# proxy.net
KiCad netlist of a schematic drawn in EAGLE
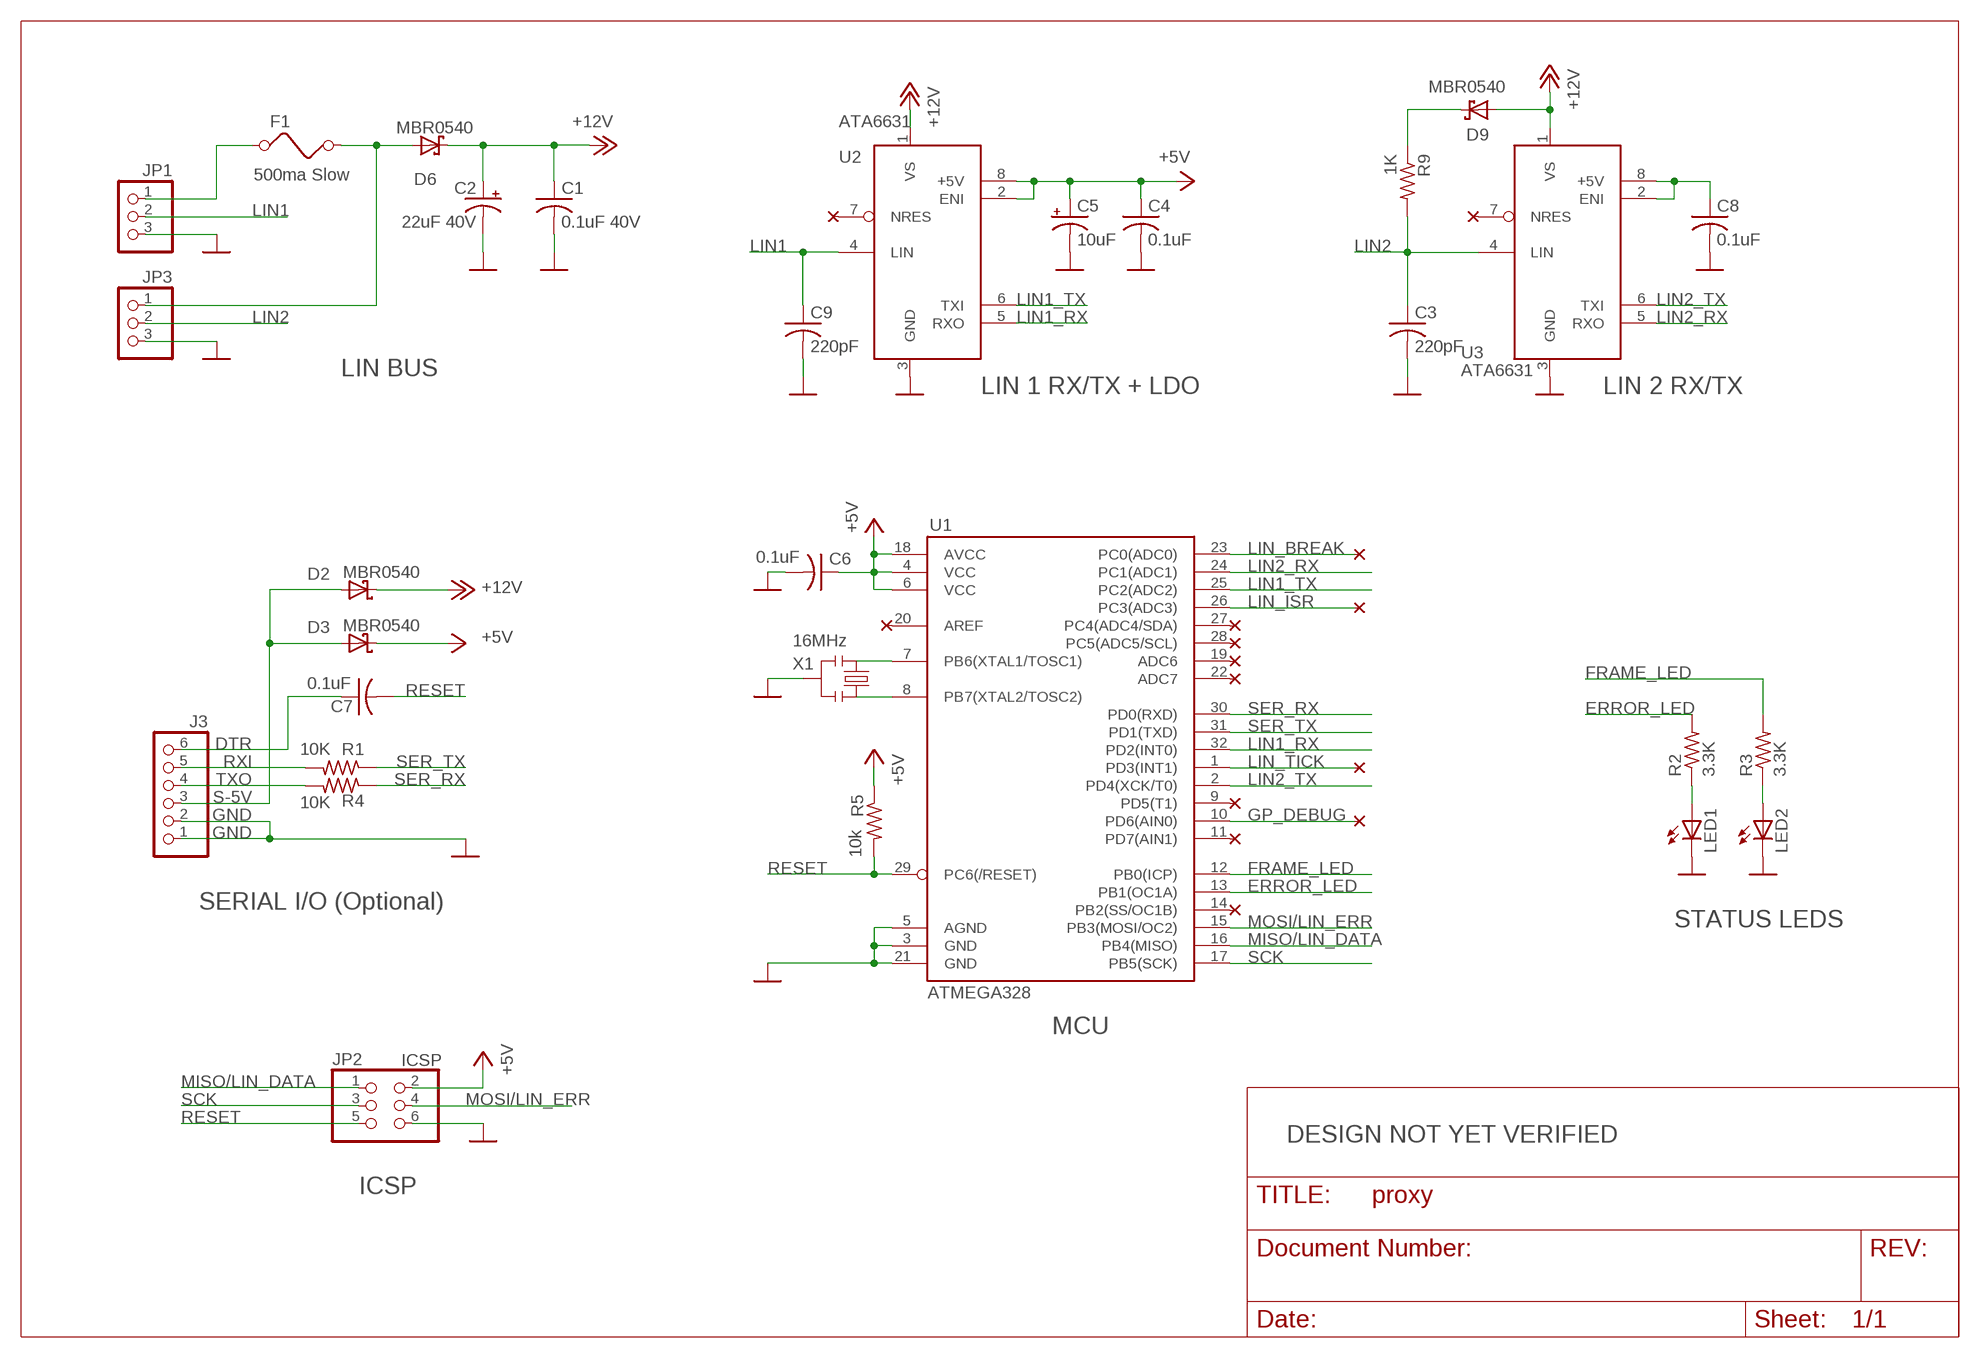
[diagram p0: schematic, sheet 1]

(export (version "E")
  (design (tool "Eeschema 10.0.6"))
  (components
    (comp (ref "C1")
      (value "0.1uF 40V")
      (footprint "eagle-import:C0805")
      (libsource (lib "eagle-import") (part "C-USC0805"))
    )
    (comp (ref "C2")
      (value "22uF 40V")
      (footprint "eagle-import:UD-6,3X5,8_NICHICON")
      (libsource (lib "eagle-import") (part "CPOL-USUD-6,3X5,8"))
    )
    (comp (ref "C3")
      (value "220pF")
      (footprint "eagle-import:C0805")
      (libsource (lib "eagle-import") (part "C-USC0805"))
    )
    (comp (ref "C4")
      (value "0.1uF")
      (footprint "eagle-import:C0805")
      (libsource (lib "eagle-import") (part "C-USC0805"))
    )
    (comp (ref "C5")
      (value "10uF")
      (footprint "eagle-import:A_3216-18R")
      (libsource (lib "eagle-import") (part "CPOL-USA/3216-18R"))
    )
    (comp (ref "C6")
      (value "0.1uF")
      (footprint "eagle-import:C0805")
      (libsource (lib "eagle-import") (part "C-USC0805"))
    )
    (comp (ref "C7")
      (value "0.1uF")
      (footprint "eagle-import:C0805")
      (libsource (lib "eagle-import") (part "C-USC0805"))
    )
    (comp (ref "C8")
      (value "0.1uF")
      (footprint "eagle-import:C0805")
      (libsource (lib "eagle-import") (part "C-USC0805"))
    )
    (comp (ref "C9")
      (value "220pF")
      (footprint "eagle-import:C0805")
      (libsource (lib "eagle-import") (part "C-USC0805"))
    )
    (comp (ref "D2")
      (value "MBR0540")
      (footprint "eagle-import:SOD123FL")
      (libsource (lib "eagle-import") (part "SMF5.0AT1"))
    )
    (comp (ref "D3")
      (value "MBR0540")
      (footprint "eagle-import:SOD123FL")
      (libsource (lib "eagle-import") (part "SMF5.0AT1"))
    )
    (comp (ref "D6")
      (value "MBR0540")
      (footprint "eagle-import:SOD123FL")
      (libsource (lib "eagle-import") (part "SMF5.0AT1"))
    )
    (comp (ref "D9")
      (value "MBR0540")
      (footprint "eagle-import:SOD123FL")
      (libsource (lib "eagle-import") (part "SMF5.0AT1"))
    )
    (comp (ref "F1")
      (value "500ma Slow")
      (footprint "eagle-import:1206")
      (libsource (lib "eagle-import") (part "FUSE"))
    )
    (comp (ref "J3")
      (value "PINHD-1X6")
      (footprint "eagle-import:1X06")
      (libsource (lib "eagle-import") (part "PINHD-1X6"))
    )
    (comp (ref "JP1")
      (value "PINHD-1X3")
      (footprint "eagle-import:1X03")
      (libsource (lib "eagle-import") (part "PINHD-1X3"))
    )
    (comp (ref "JP2")
      (value "ICSP")
      (footprint "eagle-import:2X03")
      (libsource (lib "eagle-import") (part "PINHD-2X3"))
    )
    (comp (ref "JP3")
      (value "PINHD-1X3")
      (footprint "eagle-import:1X03")
      (libsource (lib "eagle-import") (part "PINHD-1X3"))
    )
    (comp (ref "LED1")
      (value "LED")
      (footprint "eagle-import:1206-LED")
      (libsource (lib "eagle-import") (part "LED"))
    )
    (comp (ref "LED2")
      (value "LED")
      (footprint "eagle-import:1206-LED")
      (libsource (lib "eagle-import") (part "LED"))
    )
    (comp (ref "R1")
      (value "10K")
      (footprint "eagle-import:R0805")
      (libsource (lib "eagle-import") (part "R-US_R0805"))
    )
    (comp (ref "R2")
      (value "3.3K")
      (footprint "eagle-import:R0805")
      (libsource (lib "eagle-import") (part "R-US_R0805"))
    )
    (comp (ref "R3")
      (value "3.3K")
      (footprint "eagle-import:R0805")
      (libsource (lib "eagle-import") (part "R-US_R0805"))
    )
    (comp (ref "R4")
      (value "10K")
      (footprint "eagle-import:R0805")
      (libsource (lib "eagle-import") (part "R-US_R0805"))
    )
    (comp (ref "R5")
      (value "10k")
      (footprint "eagle-import:R0805")
      (libsource (lib "eagle-import") (part "R-US_R0805"))
    )
    (comp (ref "R9")
      (value "1K")
      (footprint "eagle-import:R0805")
      (libsource (lib "eagle-import") (part "R-US_R0805"))
    )
    (comp (ref "U1")
      (value "ATMEGA328")
      (footprint "eagle-import:TQFP32-08")
      (libsource (lib "eagle-import") (part "ATMEGA328"))
    )
    (comp (ref "U2")
      (value "ATA6631")
      (footprint "eagle-import:SO-08")
      (libsource (lib "eagle-import") (part "ATA6631"))
    )
    (comp (ref "U3")
      (value "ATA6631")
      (footprint "eagle-import:SO-08")
      (libsource (lib "eagle-import") (part "ATA6631"))
    )
    (comp (ref "X1")
      (value "16MHz")
      (footprint "eagle-import:RESONATOR-SMD")
      (libsource (lib "eagle-import") (part "RESONATORSMD"))
    )
  )
  (nets
    (net (code "1") (name "+5V") (class "Default")
      (node (ref "C4") (pin "1") (pinfunction "1_1") (pintype "passive"))
      (node (ref "C5") (pin "+") (pinfunction "+_+") (pintype "passive"))
      (node (ref "C6") (pin "1") (pinfunction "1_1") (pintype "passive"))
      (node (ref "D3") (pin "C") (pinfunction "C_C") (pintype "passive"))
      (node (ref "JP2") (pin "2") (pinfunction "2_2") (pintype "passive"))
      (node (ref "R5") (pin "1") (pinfunction "1_1") (pintype "passive"))
      (node (ref "U1") (pin "18") (pinfunction "AVCC_18") (pintype "power_in"))
      (node (ref "U1") (pin "4") (pinfunction "VCC_4") (pintype "power_in"))
      (node (ref "U1") (pin "6") (pinfunction "VCC_6") (pintype "power_in"))
      (node (ref "U2") (pin "2") (pinfunction "ENI_2") (pintype "input"))
      (node (ref "U2") (pin "8") (pinfunction "+5V_8") (pintype "power_in"))
    )
    (net (code "2") (name "+12V") (class "Default")
      (node (ref "C1") (pin "1") (pinfunction "1_1") (pintype "passive"))
      (node (ref "C2") (pin "+") (pinfunction "+_+") (pintype "passive"))
      (node (ref "D2") (pin "C") (pinfunction "C_C") (pintype "passive"))
      (node (ref "D6") (pin "C") (pinfunction "C_C") (pintype "passive"))
      (node (ref "D9") (pin "A") (pinfunction "A_A") (pintype "passive"))
      (node (ref "U2") (pin "1") (pinfunction "VS_1") (pintype "power_in"))
      (node (ref "U3") (pin "1") (pinfunction "VS_1") (pintype "power_in"))
    )
    (net (code "3") (name "/AREF") (class "Default")
      (node (ref "U1") (pin "20") (pinfunction "AREF_20") (pintype "power_in"))
    )
    (net (code "4") (name "/DTR") (class "Default")
      (node (ref "C7") (pin "1") (pinfunction "1_1") (pintype "passive"))
      (node (ref "J3") (pin "6") (pinfunction "6_6") (pintype "passive"))
    )
    (net (code "5") (name "/ERROR_LED") (class "Default")
      (node (ref "R2") (pin "2") (pinfunction "2_2") (pintype "passive"))
      (node (ref "U1") (pin "13") (pinfunction "PB1(OC1A)_13") (pintype "bidirectional"))
    )
    (net (code "6") (name "/FRAME_LED") (class "Default")
      (node (ref "R3") (pin "2") (pinfunction "2_2") (pintype "passive"))
      (node (ref "U1") (pin "12") (pinfunction "PB0(ICP)_12") (pintype "bidirectional"))
    )
    (net (code "7") (name "/GP_DEBUG") (class "Default")
      (node (ref "U1") (pin "10") (pinfunction "PD6(AIN0)_10") (pintype "bidirectional"))
    )
    (net (code "8") (name "/LIN1") (class "Default")
      (node (ref "C9") (pin "1") (pinfunction "1_1") (pintype "passive"))
      (node (ref "JP1") (pin "2") (pinfunction "2_2") (pintype "passive"))
      (node (ref "U2") (pin "4") (pinfunction "LIN_4") (pintype "bidirectional"))
    )
    (net (code "9") (name "/LIN1_RX") (class "Default")
      (node (ref "U1") (pin "32") (pinfunction "PD2(INT0)_32") (pintype "bidirectional"))
      (node (ref "U2") (pin "5") (pinfunction "RXO_5") (pintype "output"))
    )
    (net (code "10") (name "/LIN1_TX") (class "Default")
      (node (ref "U1") (pin "25") (pinfunction "PC2(ADC2)_25") (pintype "bidirectional"))
      (node (ref "U2") (pin "6") (pinfunction "TXI_6") (pintype "input"))
    )
    (net (code "11") (name "/LIN2") (class "Default")
      (node (ref "C3") (pin "1") (pinfunction "1_1") (pintype "passive"))
      (node (ref "JP3") (pin "2") (pinfunction "2_2") (pintype "passive"))
      (node (ref "R9") (pin "2") (pinfunction "2_2") (pintype "passive"))
      (node (ref "U3") (pin "4") (pinfunction "LIN_4") (pintype "bidirectional"))
    )
    (net (code "12") (name "/LIN2_RX") (class "Default")
      (node (ref "U1") (pin "24") (pinfunction "PC1(ADC1)_24") (pintype "bidirectional"))
      (node (ref "U3") (pin "5") (pinfunction "RXO_5") (pintype "output"))
    )
    (net (code "13") (name "/LIN2_TX") (class "Default")
      (node (ref "U1") (pin "2") (pinfunction "PD4(XCK/T0)_2") (pintype "bidirectional"))
      (node (ref "U3") (pin "6") (pinfunction "TXI_6") (pintype "input"))
    )
    (net (code "14") (name "/LIN_BREAK") (class "Default")
      (node (ref "U1") (pin "23") (pinfunction "PC0(ADC0)_23") (pintype "bidirectional"))
    )
    (net (code "15") (name "/LIN_ISR") (class "Default")
      (node (ref "U1") (pin "26") (pinfunction "PC3(ADC3)_26") (pintype "bidirectional"))
    )
    (net (code "16") (name "/LIN_TICK") (class "Default")
      (node (ref "U1") (pin "1") (pinfunction "PD3(INT1)_1") (pintype "bidirectional"))
    )
    (net (code "17") (name "/MISO{slash}LIN_DATA") (class "Default")
      (node (ref "JP2") (pin "1") (pinfunction "1_1") (pintype "passive"))
      (node (ref "U1") (pin "16") (pinfunction "PB4(MISO)_16") (pintype "bidirectional"))
    )
    (net (code "18") (name "/MOSI{slash}LIN_ERR") (class "Default")
      (node (ref "JP2") (pin "4") (pinfunction "4_4") (pintype "passive"))
      (node (ref "U1") (pin "15") (pinfunction "PB3(MOSI/OC2)_15") (pintype "bidirectional"))
    )
    (net (code "19") (name "/RESET") (class "Default")
      (node (ref "C7") (pin "2") (pinfunction "2_2") (pintype "passive"))
      (node (ref "JP2") (pin "5") (pinfunction "5_5") (pintype "passive"))
      (node (ref "R5") (pin "2") (pinfunction "2_2") (pintype "passive"))
      (node (ref "U1") (pin "29") (pinfunction "PC6(/RESET)_29") (pintype "bidirectional"))
    )
    (net (code "20") (name "/RXI") (class "Default")
      (node (ref "J3") (pin "5") (pinfunction "5_5") (pintype "passive"))
      (node (ref "R1") (pin "2") (pinfunction "2_2") (pintype "passive"))
    )
    (net (code "21") (name "/S-5V") (class "Default")
      (node (ref "D2") (pin "A") (pinfunction "A_A") (pintype "passive"))
      (node (ref "D3") (pin "A") (pinfunction "A_A") (pintype "passive"))
      (node (ref "J3") (pin "3") (pinfunction "3_3") (pintype "passive"))
    )
    (net (code "22") (name "/SCK") (class "Default")
      (node (ref "JP2") (pin "3") (pinfunction "3_3") (pintype "passive"))
      (node (ref "U1") (pin "17") (pinfunction "PB5(SCK)_17") (pintype "bidirectional"))
    )
    (net (code "23") (name "/SER_RX") (class "Default")
      (node (ref "R4") (pin "1") (pinfunction "1_1") (pintype "passive"))
      (node (ref "U1") (pin "30") (pinfunction "PD0(RXD)_30") (pintype "bidirectional"))
    )
    (net (code "24") (name "/SER_TX") (class "Default")
      (node (ref "R1") (pin "1") (pinfunction "1_1") (pintype "passive"))
      (node (ref "U1") (pin "31") (pinfunction "PD1(TXD)_31") (pintype "bidirectional"))
    )
    (net (code "25") (name "/TXO") (class "Default")
      (node (ref "J3") (pin "4") (pinfunction "4_4") (pintype "passive"))
      (node (ref "R4") (pin "2") (pinfunction "2_2") (pintype "passive"))
    )
    (net (code "26") (name "GND") (class "Default")
      (node (ref "C1") (pin "2") (pinfunction "2_2") (pintype "passive"))
      (node (ref "C2") (pin "-") (pinfunction "-_-") (pintype "passive"))
      (node (ref "C3") (pin "2") (pinfunction "2_2") (pintype "passive"))
      (node (ref "C4") (pin "2") (pinfunction "2_2") (pintype "passive"))
      (node (ref "C5") (pin "-") (pinfunction "-_-") (pintype "passive"))
      (node (ref "C6") (pin "2") (pinfunction "2_2") (pintype "passive"))
      (node (ref "C8") (pin "2") (pinfunction "2_2") (pintype "passive"))
      (node (ref "C9") (pin "2") (pinfunction "2_2") (pintype "passive"))
      (node (ref "J3") (pin "1") (pinfunction "1_1") (pintype "passive"))
      (node (ref "J3") (pin "2") (pinfunction "2_2") (pintype "passive"))
      (node (ref "JP1") (pin "3") (pinfunction "3_3") (pintype "passive"))
      (node (ref "JP2") (pin "6") (pinfunction "6_6") (pintype "passive"))
      (node (ref "JP3") (pin "3") (pinfunction "3_3") (pintype "passive"))
      (node (ref "LED1") (pin "C") (pinfunction "C_C") (pintype "passive"))
      (node (ref "LED2") (pin "C") (pinfunction "C_C") (pintype "passive"))
      (node (ref "U1") (pin "21") (pinfunction "GND_21") (pintype "power_in"))
      (node (ref "U1") (pin "3") (pinfunction "GND_3") (pintype "power_in"))
      (node (ref "U1") (pin "5") (pinfunction "AGND_5") (pintype "power_in"))
      (node (ref "U2") (pin "3") (pinfunction "GND_3") (pintype "power_in"))
      (node (ref "U3") (pin "3") (pinfunction "GND_3") (pintype "power_in"))
      (node (ref "X1") (pin "2") (pinfunction "2_2") (pintype "passive"))
    )
    (net (code "27") (name "Net-(D6-PadA)") (class "Default")
      (node (ref "D6") (pin "A") (pinfunction "A_A") (pintype "passive"))
      (node (ref "F1") (pin "2") (pinfunction "2_2") (pintype "passive"))
      (node (ref "JP3") (pin "1") (pinfunction "1_1") (pintype "passive"))
    )
    (net (code "28") (name "Net-(D9-PadC)") (class "Default")
      (node (ref "D9") (pin "C") (pinfunction "C_C") (pintype "passive"))
      (node (ref "R9") (pin "1") (pinfunction "1_1") (pintype "passive"))
    )
    (net (code "29") (name "Net-(F1-Pad1)") (class "Default")
      (node (ref "F1") (pin "1") (pinfunction "1_1") (pintype "passive"))
      (node (ref "JP1") (pin "1") (pinfunction "1_1") (pintype "passive"))
    )
    (net (code "30") (name "Net-(LED1-PadA)") (class "Default")
      (node (ref "LED1") (pin "A") (pinfunction "A_A") (pintype "passive"))
      (node (ref "R2") (pin "1") (pinfunction "1_1") (pintype "passive"))
    )
    (net (code "31") (name "Net-(LED2-PadA)") (class "Default")
      (node (ref "LED2") (pin "A") (pinfunction "A_A") (pintype "passive"))
      (node (ref "R3") (pin "1") (pinfunction "1_1") (pintype "passive"))
    )
    (net (code "32") (name "Net-(U1-PB6(XTAL1{slash}TOSC1))") (class "Default")
      (node (ref "U1") (pin "7") (pinfunction "PB6(XTAL1/TOSC1)_7") (pintype "bidirectional"))
      (node (ref "X1") (pin "3") (pinfunction "3_3") (pintype "passive"))
    )
    (net (code "33") (name "Net-(U1-PB7(XTAL2{slash}TOSC2))") (class "Default")
      (node (ref "U1") (pin "8") (pinfunction "PB7(XTAL2/TOSC2)_8") (pintype "bidirectional"))
      (node (ref "X1") (pin "1") (pinfunction "1_1") (pintype "passive"))
    )
    (net (code "34") (name "Net-(U3-+5V)") (class "Default")
      (node (ref "C8") (pin "1") (pinfunction "1_1") (pintype "passive"))
      (node (ref "U3") (pin "2") (pinfunction "ENI_2") (pintype "input"))
      (node (ref "U3") (pin "8") (pinfunction "+5V_8") (pintype "power_in"))
    )
    (net (code "35") (name "unconnected-(U1-ADC6-Pad19)") (class "Default")
      (node (ref "U1") (pin "19") (pinfunction "ADC6_19") (pintype "bidirectional"))
    )
    (net (code "36") (name "unconnected-(U1-ADC7-Pad22)") (class "Default")
      (node (ref "U1") (pin "22") (pinfunction "ADC7_22") (pintype "bidirectional"))
    )
    (net (code "37") (name "unconnected-(U1-PB2(SS{slash}OC1B)-Pad14)") (class "Default")
      (node (ref "U1") (pin "14") (pinfunction "PB2(SS/OC1B)_14") (pintype "bidirectional"))
    )
    (net (code "38") (name "unconnected-(U1-PC4(ADC4{slash}SDA)-Pad27)") (class "Default")
      (node (ref "U1") (pin "27") (pinfunction "PC4(ADC4/SDA)_27") (pintype "bidirectional"))
    )
    (net (code "39") (name "unconnected-(U1-PC5(ADC5{slash}SCL)-Pad28)") (class "Default")
      (node (ref "U1") (pin "28") (pinfunction "PC5(ADC5/SCL)_28") (pintype "bidirectional"))
    )
    (net (code "40") (name "unconnected-(U1-PD5(T1)-Pad9)") (class "Default")
      (node (ref "U1") (pin "9") (pinfunction "PD5(T1)_9") (pintype "bidirectional"))
    )
    (net (code "41") (name "unconnected-(U1-PD7(AIN1)-Pad11)") (class "Default")
      (node (ref "U1") (pin "11") (pinfunction "PD7(AIN1)_11") (pintype "bidirectional"))
    )
    (net (code "42") (name "unconnected-(U2-NRES-Pad7)") (class "Default")
      (node (ref "U2") (pin "7") (pinfunction "NRES_7") (pintype "output"))
    )
    (net (code "43") (name "unconnected-(U3-NRES-Pad7)") (class "Default")
      (node (ref "U3") (pin "7") (pinfunction "NRES_7") (pintype "output"))
    )
  )
)
